# UC3844_-_SIN_TEST_GENERA_MODELO.net
KiCad netlist of a schematic drawn in Altium Designer
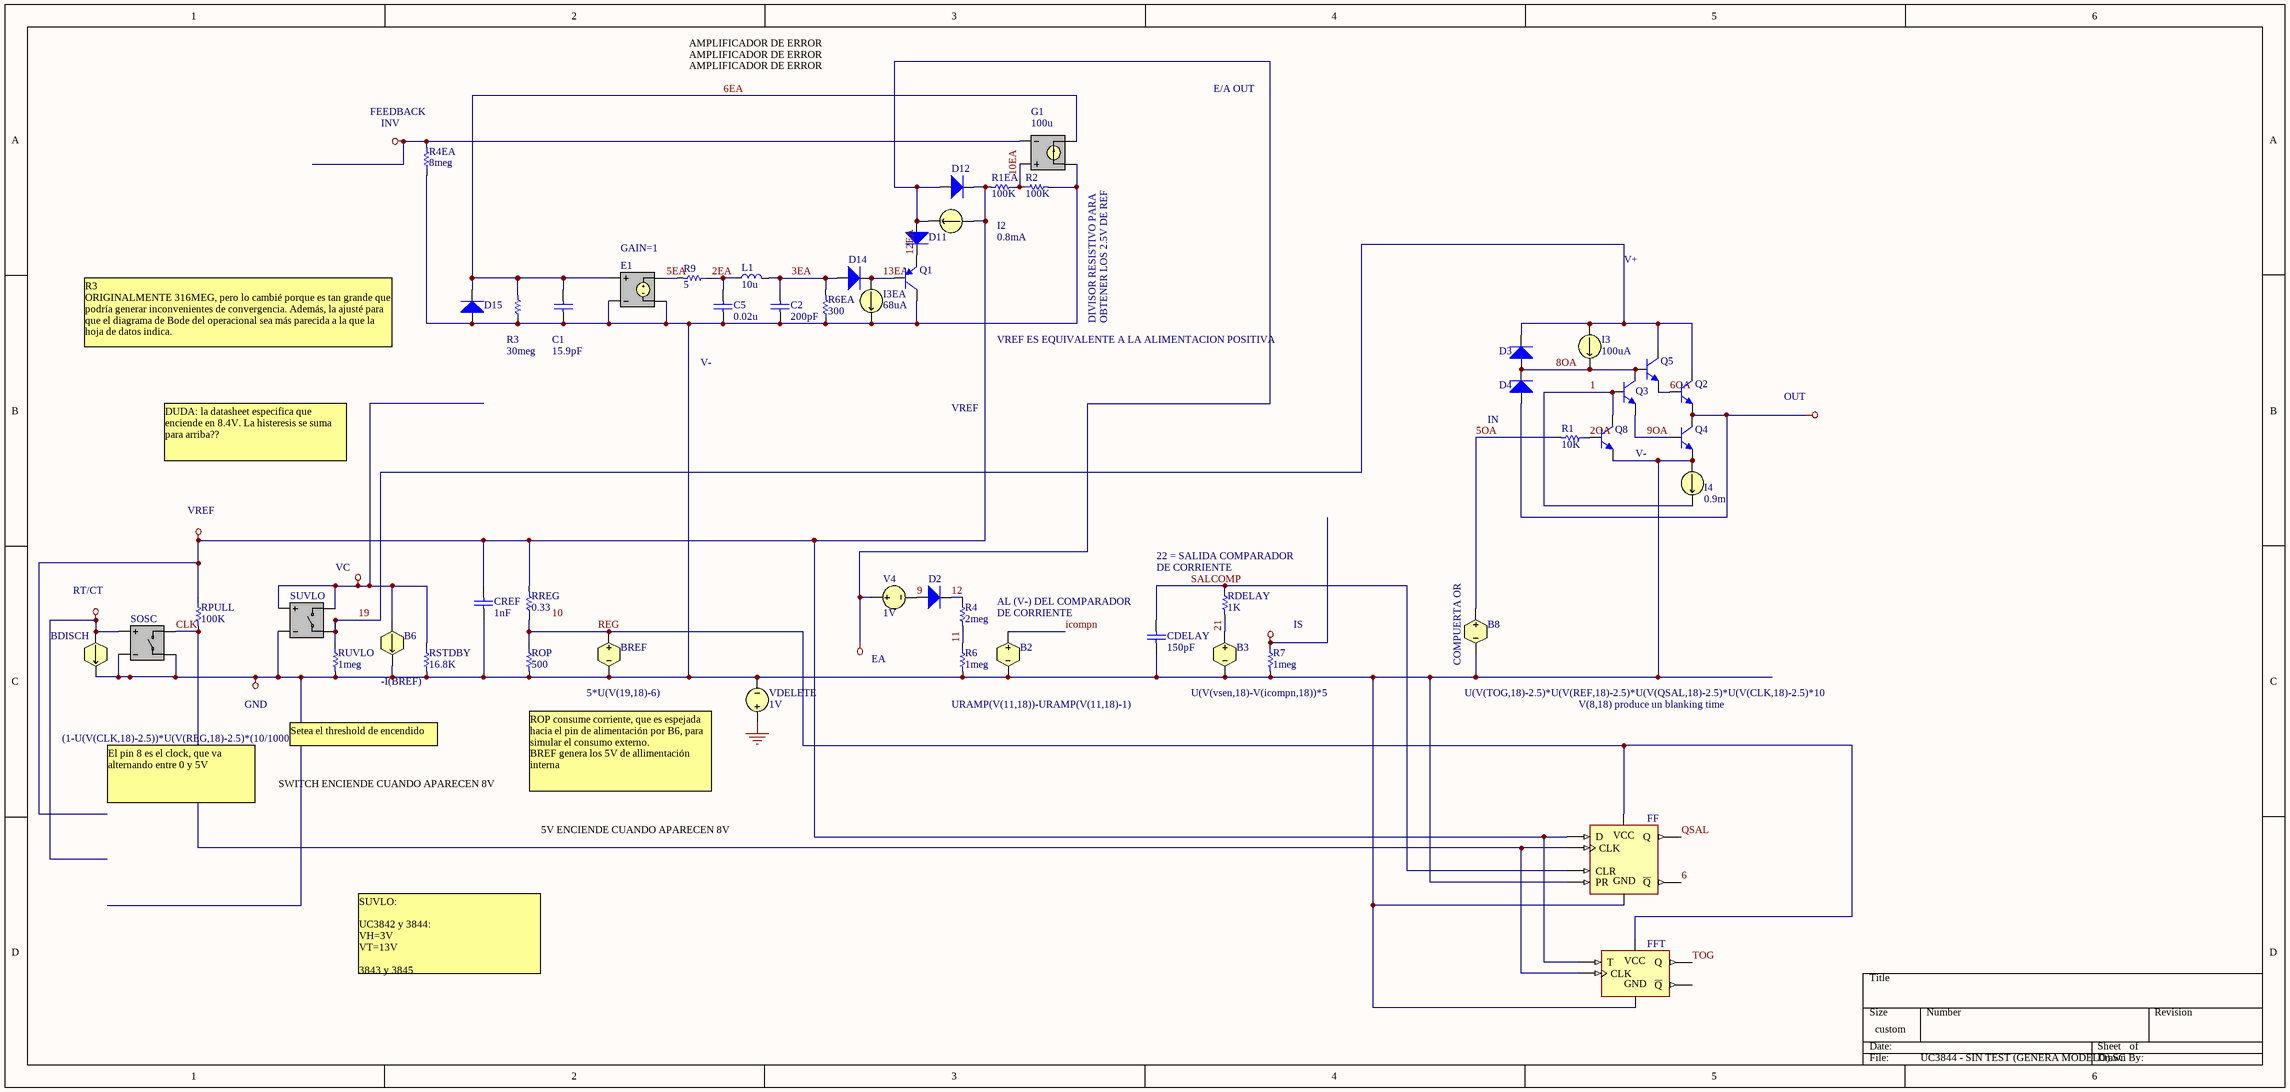
[diagram p0: UC3844 - SIN TEST (GENERA MODELO).SCHDOC]

(export (version "E")
  (design (tool "Eeschema 10.0.6"))
  (components
    (comp (ref "B2")
      (value "BVSRC")
      (description "Non-Linear Dependent Voltage Source")
      (fields
        (field (name "EQUATION") "URAMP(V(11,18))-URAMP(V(11,18)-1)")
        (field (name "PUBLISHER") "Altium Limited")
      )
      (libsource (lib "Simulation Sources") (part "BVSRC"))
    )
    (comp (ref "B3")
      (value "BVSRC")
      (description "Non-Linear Dependent Voltage Source")
      (fields
        (field (name "EQUATION") "U(V(vsen,18)-V(icompn,18))*5")
        (field (name "PUBLISHER") "Altium Limited")
      )
      (libsource (lib "Simulation Sources") (part "BVSRC"))
    )
    (comp (ref "B6")
      (value "BISRC")
      (description "Non-Linear Dependent Current Source")
      (fields (field (name "EQUATION") "-I(BREF)") (field (name "PUBLISHER") "Altium Limited"))
      (libsource (lib "Simulation Sources") (part "BISRC"))
    )
    (comp (ref "B8")
      (value "BVSRC")
      (description "Non-Linear Dependent Voltage Source")
      (fields
        (field (name "EQUATION") "U(V(TOG,18)-2.5)*U(V(REF,18)-2.5)*U(V(QSAL,18)-2.5)*U(V(CLK,18)-2.5)*10")
        (field (name "PUBLISHER") "Altium Limited")
      )
      (libsource (lib "Simulation Sources") (part "BVSRC"))
    )
    (comp (ref "BDISCH")
      (value "BISRC")
      (description "Non-Linear Dependent Current Source")
      (fields
        (field (name "EQUATION") "(1-U(V(CLK,18)-2.5))*U(V(REG,18)-2.5)*(10/1000)")
        (field (name "PUBLISHER") "Altium Limited")
      )
      (libsource (lib "Simulation Sources") (part "BISRC"))
    )
    (comp (ref "BREF")
      (value "BVSRC")
      (description "Non-Linear Dependent Voltage Source")
      (fields (field (name "EQUATION") "5*U(V(19,18)-6)") (field (name "PUBLISHER") "Altium Limited"))
      (libsource (lib "Simulation Sources") (part "BVSRC"))
    )
    (comp (ref "C1")
      (value "15.9pF")
      (footprint "0805")
      (description "Capacitor")
      (fields (field (name "VOLTAGE") "50V") (field (name "Comment") "Cap"))
      (libsource (lib "FEDE") (part "Cap"))
    )
    (comp (ref "C2")
      (value "200pF")
      (footprint "0805")
      (description "Capacitor")
      (fields (field (name "VOLTAGE") "50V") (field (name "Comment") "Cap"))
      (libsource (lib "FEDE") (part "Cap"))
    )
    (comp (ref "C5")
      (value "0.02u")
      (footprint "0805")
      (description "Capacitor")
      (fields (field (name "VOLTAGE") "50V") (field (name "Comment") "Cap"))
      (libsource (lib "FEDE") (part "Cap"))
    )
    (comp (ref "CDELAY")
      (value "150pF")
      (footprint "0805")
      (description "Capacitor")
      (fields (field (name "VOLTAGE") "50V") (field (name "Comment") "Cap"))
      (libsource (lib "FEDE") (part "Cap"))
    )
    (comp (ref "CREF")
      (value "1nF")
      (footprint "0805")
      (description "Capacitor")
      (fields (field (name "VOLTAGE") "50V") (field (name "Comment") "Cap"))
      (libsource (lib "FEDE") (part "Cap"))
    )
    (comp (ref "D2")
      (value "Diode")
      (footprint "diode400")
      (description "Diodo")
      (libsource (lib "FEDE") (part "Diode"))
    )
    (comp (ref "D3")
      (value "Diode")
      (footprint "diode400")
      (description "Diodo")
      (libsource (lib "FEDE") (part "Diode"))
    )
    (comp (ref "D4")
      (value "Diode")
      (footprint "diode400")
      (description "Diodo")
      (libsource (lib "FEDE") (part "Diode"))
    )
    (comp (ref "D11")
      (value "Diode")
      (footprint "diode400")
      (description "Diodo")
      (libsource (lib "FEDE") (part "Diode"))
    )
    (comp (ref "D12")
      (value "Diode")
      (footprint "diode400")
      (description "Diodo")
      (libsource (lib "FEDE") (part "Diode"))
    )
    (comp (ref "D14")
      (value "Diode")
      (footprint "diode400")
      (description "Diodo")
      (libsource (lib "FEDE") (part "Diode"))
    )
    (comp (ref "D15")
      (value "Diode")
      (footprint "diode400")
      (description "Diodo")
      (libsource (lib "FEDE") (part "Diode"))
    )
    (comp (ref "E1")
      (value "ESRC")
      (description "Voltage Controlled Voltage Source")
      (fields (field (name "PUBLISHER") "Altium Limited"))
      (libsource (lib "Simulation Sources") (part "ESRC"))
    )
    (comp (ref "FF")
      (value "FFSRV2")
      (description "D-Type Positive-Edge-Triggered Flip-Flop with Clear and Preset (simulación)")
      (libsource (lib "FEDE") (part "FFSRV2"))
    )
    (comp (ref "FFT")
      (value "FFT")
      (description "Positive-Edge-Triggered Flip-Flop T (simulación)")
      (libsource (lib "FEDE") (part "FFT"))
    )
    (comp (ref "G1")
      (value "GSRC")
      (description "Voltage Controlled Current Source")
      (fields (field (name "GAIN") "100u") (field (name "PUBLISHER") "Altium Limited"))
      (libsource (lib "Simulation Sources") (part "GSRC"))
    )
    (comp (ref "I2")
      (value "0.8mA")
      (description "Current Source")
      (fields (field (name "Comment") "ISRC") (field (name "PUBLISHER") "Altium Limited"))
      (libsource (lib "Simulation Sources") (part "ISRC"))
    )
    (comp (ref "I3")
      (value "100uA")
      (description "Current Source")
      (fields (field (name "Comment") "ISRC") (field (name "PUBLISHER") "Altium Limited"))
      (libsource (lib "Simulation Sources") (part "ISRC"))
    )
    (comp (ref "I3EA")
      (value "68uA")
      (description "Current Source")
      (fields (field (name "Comment") "ISRC") (field (name "PUBLISHER") "Altium Limited"))
      (libsource (lib "Simulation Sources") (part "ISRC"))
    )
    (comp (ref "I4")
      (value "0.9m")
      (description "Current Source")
      (fields (field (name "Comment") "ISRC") (field (name "PUBLISHER") "Altium Limited"))
      (libsource (lib "Simulation Sources") (part "ISRC"))
    )
    (comp (ref "L1")
      (value "10u")
      (footprint "TOROIDE TN14-9-5")
      (description "Inductor")
      (fields (field (name "Comment") "Inductor2"))
      (libsource (lib "FEDE") (part "Inductor2"))
    )
    (comp (ref "Q1")
      (value "PNP")
      (footprint "SOT23")
      (description "PNP Bipolar Transistor")
      (libsource (lib "FEDE") (part "PNP"))
    )
    (comp (ref "Q2")
      (value "NPN")
      (footprint "SOT23")
      (description "NPN Bipolar Transistor")
      (libsource (lib "FEDE") (part "NPN"))
    )
    (comp (ref "Q3")
      (value "NPN")
      (footprint "SOT23")
      (description "NPN Bipolar Transistor")
      (libsource (lib "FEDE") (part "NPN"))
    )
    (comp (ref "Q4")
      (value "NPN")
      (footprint "SOT23")
      (description "NPN Bipolar Transistor")
      (libsource (lib "FEDE") (part "NPN"))
    )
    (comp (ref "Q5")
      (value "NPN")
      (footprint "SOT23")
      (description "NPN Bipolar Transistor")
      (libsource (lib "FEDE") (part "NPN"))
    )
    (comp (ref "Q8")
      (value "NPN")
      (footprint "SOT23")
      (description "NPN Bipolar Transistor")
      (libsource (lib "FEDE") (part "NPN"))
    )
    (comp (ref "R1")
      (value "10K")
      (footprint "0805")
      (description "Resistor")
      (fields (field (name "POWER") "0.25W") (field (name "Comment") "Res"))
      (libsource (lib "FEDE") (part "Res"))
    )
    (comp (ref "R1EA")
      (value "100K")
      (footprint "0805")
      (description "Resistor")
      (fields (field (name "POWER") "0.25W") (field (name "Comment") "Res"))
      (libsource (lib "FEDE") (part "Res"))
    )
    (comp (ref "R2")
      (value "100K")
      (footprint "0805")
      (description "Resistor")
      (fields (field (name "POWER") "0.25W") (field (name "Comment") "Res"))
      (libsource (lib "FEDE") (part "Res"))
    )
    (comp (ref "R3")
      (value "30meg")
      (footprint "0805")
      (description "Resistor")
      (fields (field (name "POWER") "0.25W") (field (name "Comment") "Res"))
      (libsource (lib "FEDE") (part "Res"))
    )
    (comp (ref "R4")
      (value "2meg")
      (footprint "0805")
      (description "Resistor")
      (fields (field (name "POWER") "0.25W") (field (name "Comment") "Res"))
      (libsource (lib "FEDE") (part "Res"))
    )
    (comp (ref "R4EA")
      (value "8meg")
      (footprint "0805")
      (description "Resistor")
      (fields (field (name "POWER") "0.25W") (field (name "Comment") "Res"))
      (libsource (lib "FEDE") (part "Res"))
    )
    (comp (ref "R6")
      (value "1meg")
      (footprint "0805")
      (description "Resistor")
      (fields (field (name "POWER") "0.25W") (field (name "Comment") "Res"))
      (libsource (lib "FEDE") (part "Res"))
    )
    (comp (ref "R6EA")
      (value "300")
      (footprint "0805")
      (description "Resistor")
      (fields (field (name "POWER") "0.25W") (field (name "Comment") "Res"))
      (libsource (lib "FEDE") (part "Res"))
    )
    (comp (ref "R7")
      (value "1meg")
      (footprint "0805")
      (description "Resistor")
      (fields (field (name "POWER") "0.25W") (field (name "Comment") "Res"))
      (libsource (lib "FEDE") (part "Res"))
    )
    (comp (ref "R9")
      (value "5")
      (footprint "0805")
      (description "Resistor")
      (fields (field (name "POWER") "0.25W") (field (name "Comment") "Res"))
      (libsource (lib "FEDE") (part "Res"))
    )
    (comp (ref "RDELAY")
      (value "1K")
      (footprint "0805")
      (description "Resistor")
      (fields (field (name "POWER") "0.25W") (field (name "Comment") "Res"))
      (libsource (lib "FEDE") (part "Res"))
    )
    (comp (ref "ROP")
      (value "500")
      (footprint "0805")
      (description "Resistor")
      (fields (field (name "POWER") "0.25W") (field (name "Comment") "Res"))
      (libsource (lib "FEDE") (part "Res"))
    )
    (comp (ref "RPULL")
      (value "100K")
      (footprint "0805")
      (description "Resistor")
      (fields (field (name "POWER") "0.25W") (field (name "Comment") "Res"))
      (libsource (lib "FEDE") (part "Res"))
    )
    (comp (ref "RREG")
      (value "0.33")
      (footprint "0805")
      (description "Resistor")
      (fields (field (name "POWER") "0.25W") (field (name "Comment") "Res"))
      (libsource (lib "FEDE") (part "Res"))
    )
    (comp (ref "RSTDBY")
      (value "16.8K")
      (footprint "0805")
      (description "Resistor")
      (fields (field (name "POWER") "0.25W") (field (name "Comment") "Res"))
      (libsource (lib "FEDE") (part "Res"))
    )
    (comp (ref "RUVLO")
      (value "1meg")
      (footprint "0805")
      (description "Resistor")
      (fields (field (name "POWER") "0.25W") (field (name "Comment") "Res"))
      (libsource (lib "FEDE") (part "Res"))
    )
    (comp (ref "SOSC")
      (value "VSW")
      (description "Voltage Controlled Switch (simulación)")
      (libsource (lib "FEDE") (part "VSW"))
    )
    (comp (ref "SUVLO")
      (value "VSW")
      (description "Voltage Controlled Switch (simulación)")
      (libsource (lib "FEDE") (part "VSW"))
    )
    (comp (ref "V4")
      (value "1V")
      (description "Voltage Source")
      (fields (field (name "Comment") "VSRC") (field (name "PUBLISHER") "Altium Limited"))
      (libsource (lib "Simulation Sources") (part "VSRC"))
    )
    (comp (ref "VDELETE")
      (value "1V")
      (description "Voltage Source")
      (fields (field (name "Comment") "VSRC") (field (name "PUBLISHER") "Altium Limited"))
      (libsource (lib "Simulation Sources") (part "VSRC"))
    )
  )
  (nets
    (net (code "1") (name "/1") (class "Default")
      (node (ref "I4") (pin "2") (pinfunction "2_2") (pintype "passive"))
      (node (ref "Q3") (pin "2") (pinfunction "B_2") (pintype "passive"))
      (node (ref "Q8") (pin "1") (pinfunction "C_1") (pintype "passive"))
    )
    (net (code "2") (name "/2EA") (class "Default")
      (node (ref "C5") (pin "2") (pinfunction "2_2") (pintype "passive"))
      (node (ref "L1") (pin "1") (pinfunction "1_1") (pintype "passive"))
      (node (ref "R9") (pin "1") (pinfunction "1_1") (pintype "passive"))
    )
    (net (code "3") (name "/2OA") (class "Default")
      (node (ref "Q8") (pin "2") (pinfunction "B_2") (pintype "passive"))
      (node (ref "R1") (pin "1") (pinfunction "1_1") (pintype "passive"))
    )
    (net (code "4") (name "/3EA") (class "Default")
      (node (ref "C2") (pin "2") (pinfunction "2_2") (pintype "passive"))
      (node (ref "D14") (pin "1") (pinfunction "1_1") (pintype "passive"))
      (node (ref "L1") (pin "2") (pinfunction "2_2") (pintype "passive"))
      (node (ref "R6EA") (pin "2") (pinfunction "2_2") (pintype "passive"))
    )
    (net (code "5") (name "/5EA") (class "Default")
      (node (ref "E1") (pin "3") (pinfunction "N+_3") (pintype "passive"))
      (node (ref "R9") (pin "2") (pinfunction "2_2") (pintype "passive"))
    )
    (net (code "6") (name "/5OA") (class "Default")
      (node (ref "B8") (pin "1") (pinfunction "1_1") (pintype "passive"))
      (node (ref "R1") (pin "2") (pinfunction "2_2") (pintype "passive"))
    )
    (net (code "7") (name "/6") (class "Default")
      (node (ref "FF") (pin "6") (pinfunction "~{Q}_6") (pintype "output"))
    )
    (net (code "8") (name "/6EA") (class "Default")
      (node (ref "C1") (pin "2") (pinfunction "2_2") (pintype "passive"))
      (node (ref "D15") (pin "2") (pinfunction "2_2") (pintype "passive"))
      (node (ref "E1") (pin "1") (pinfunction "NC+_1") (pintype "passive"))
      (node (ref "G1") (pin "4") (pinfunction "N-_4") (pintype "passive"))
      (node (ref "R3") (pin "2") (pinfunction "2_2") (pintype "passive"))
    )
    (net (code "9") (name "/6OA") (class "Default")
      (node (ref "Q2") (pin "2") (pinfunction "B_2") (pintype "passive"))
      (node (ref "Q5") (pin "3") (pinfunction "E_3") (pintype "passive"))
    )
    (net (code "10") (name "/8OA") (class "Default")
      (node (ref "D3") (pin "1") (pinfunction "1_1") (pintype "passive"))
      (node (ref "D4") (pin "2") (pinfunction "2_2") (pintype "passive"))
      (node (ref "I3") (pin "2") (pinfunction "2_2") (pintype "passive"))
      (node (ref "Q3") (pin "1") (pinfunction "C_1") (pintype "passive"))
      (node (ref "Q5") (pin "2") (pinfunction "B_2") (pintype "passive"))
    )
    (net (code "11") (name "/9") (class "Default")
      (node (ref "D2") (pin "1") (pinfunction "1_1") (pintype "passive"))
      (node (ref "V4") (pin "2") (pinfunction "2_2") (pintype "passive"))
    )
    (net (code "12") (name "/9OA") (class "Default")
      (node (ref "Q3") (pin "3") (pinfunction "E_3") (pintype "passive"))
      (node (ref "Q4") (pin "2") (pinfunction "B_2") (pintype "passive"))
    )
    (net (code "14") (name "/10EA") (class "Default")
      (node (ref "G1") (pin "1") (pinfunction "NC+_1") (pintype "passive"))
      (node (ref "R1EA") (pin "1") (pinfunction "1_1") (pintype "passive"))
      (node (ref "R2") (pin "1") (pinfunction "1_1") (pintype "passive"))
    )
    (net (code "15") (name "/11") (class "Default")
      (node (ref "R4") (pin "2") (pinfunction "2_2") (pintype "passive"))
      (node (ref "R6") (pin "1") (pinfunction "1_1") (pintype "passive"))
    )
    (net (code "16") (name "/12") (class "Default")
      (node (ref "D2") (pin "2") (pinfunction "2_2") (pintype "passive"))
      (node (ref "R4") (pin "1") (pinfunction "1_1") (pintype "passive"))
    )
    (net (code "17") (name "/12EA") (class "Default")
      (node (ref "D11") (pin "2") (pinfunction "2_2") (pintype "passive"))
      (node (ref "Q1") (pin "3") (pinfunction "E_3") (pintype "passive"))
    )
    (net (code "18") (name "/13EA") (class "Default")
      (node (ref "D14") (pin "2") (pinfunction "2_2") (pintype "passive"))
      (node (ref "I3EA") (pin "1") (pinfunction "1_1") (pintype "passive"))
      (node (ref "Q1") (pin "2") (pinfunction "B_2") (pintype "passive"))
    )
    (net (code "19") (name "/19") (class "Default")
      (node (ref "D3") (pin "2") (pinfunction "2_2") (pintype "passive"))
      (node (ref "I3") (pin "1") (pinfunction "1_1") (pintype "passive"))
      (node (ref "Q2") (pin "1") (pinfunction "C_1") (pintype "passive"))
      (node (ref "Q5") (pin "1") (pinfunction "C_1") (pintype "passive"))
      (node (ref "RUVLO") (pin "1") (pinfunction "1_1") (pintype "passive"))
      (node (ref "SUVLO") (pin "4") (pinfunction "N2-_4") (pintype "passive"))
    )
    (net (code "20") (name "/21") (class "Default")
      (node (ref "B3") (pin "1") (pinfunction "1_1") (pintype "passive"))
      (node (ref "RDELAY") (pin "2") (pinfunction "2_2") (pintype "passive"))
    )
    (net (code "21") (name "/CLK") (class "Default")
      (node (ref "FF") (pin "3") (pinfunction "CLK_3") (pintype "input"))
      (node (ref "FFT") (pin "2") (pinfunction "CLK_2") (pintype "input"))
      (node (ref "RPULL") (pin "2") (pinfunction "2_2") (pintype "passive"))
      (node (ref "SOSC") (pin "3") (pinfunction "N2+_3") (pintype "passive"))
    )
    (net (code "22") (name "/QSAL") (class "Default")
      (node (ref "FF") (pin "5") (pinfunction "Q_5") (pintype "output"))
    )
    (net (code "23") (name "/REG") (class "Default")
      (node (ref "BREF") (pin "1") (pinfunction "1_1") (pintype "passive"))
      (node (ref "FF") (pin "14") (pinfunction "VCC_14") (pintype "power_in"))
      (node (ref "FFT") (pin "5") (pinfunction "VCC_5") (pintype "power_in"))
      (node (ref "ROP") (pin "1") (pinfunction "1_1") (pintype "passive"))
      (node (ref "RREG") (pin "1") (pinfunction "1_1") (pintype "passive"))
    )
    (net (code "24") (name "/SALCOMP") (class "Default")
      (node (ref "CDELAY") (pin "2") (pinfunction "2_2") (pintype "passive"))
      (node (ref "FF") (pin "1") (pinfunction "CLR_1") (pintype "input"))
      (node (ref "RDELAY") (pin "1") (pinfunction "1_1") (pintype "passive"))
    )
    (net (code "25") (name "/TOG") (class "Default")
      (node (ref "FFT") (pin "3") (pinfunction "Q_3") (pintype "output"))
    )
    (net (code "26") (name "/icompn") (class "Default")
      (node (ref "B2") (pin "1") (pinfunction "1_1") (pintype "passive"))
    )
    (net (code "27") (name "18") (class "Default")
      (node (ref "B2") (pin "2") (pinfunction "2_2") (pintype "passive"))
      (node (ref "B3") (pin "2") (pinfunction "2_2") (pintype "passive"))
      (node (ref "B6") (pin "2") (pinfunction "2_2") (pintype "passive"))
      (node (ref "B8") (pin "2") (pinfunction "2_2") (pintype "passive"))
      (node (ref "BDISCH") (pin "2") (pinfunction "2_2") (pintype "passive"))
      (node (ref "BREF") (pin "2") (pinfunction "2_2") (pintype "passive"))
      (node (ref "C1") (pin "1") (pinfunction "1_1") (pintype "passive"))
      (node (ref "C2") (pin "1") (pinfunction "1_1") (pintype "passive"))
      (node (ref "C5") (pin "1") (pinfunction "1_1") (pintype "passive"))
      (node (ref "CDELAY") (pin "1") (pinfunction "1_1") (pintype "passive"))
      (node (ref "CREF") (pin "1") (pinfunction "1_1") (pintype "passive"))
      (node (ref "D15") (pin "1") (pinfunction "1_1") (pintype "passive"))
      (node (ref "E1") (pin "2") (pinfunction "NC-_2") (pintype "passive"))
      (node (ref "E1") (pin "4") (pinfunction "N-_4") (pintype "passive"))
      (node (ref "FF") (pin "4") (pinfunction "PR_4") (pintype "input"))
      (node (ref "FF") (pin "7") (pinfunction "GND_7") (pintype "power_in"))
      (node (ref "FFT") (pin "6") (pinfunction "GND_6") (pintype "power_in"))
      (node (ref "G1") (pin "3") (pinfunction "N+_3") (pintype "passive"))
      (node (ref "I3EA") (pin "2") (pinfunction "2_2") (pintype "passive"))
      (node (ref "I4") (pin "1") (pinfunction "1_1") (pintype "passive"))
      (node (ref "Q1") (pin "1") (pinfunction "C_1") (pintype "passive"))
      (node (ref "Q4") (pin "3") (pinfunction "E_3") (pintype "passive"))
      (node (ref "Q8") (pin "3") (pinfunction "E_3") (pintype "passive"))
      (node (ref "R2") (pin "2") (pinfunction "2_2") (pintype "passive"))
      (node (ref "R3") (pin "1") (pinfunction "1_1") (pintype "passive"))
      (node (ref "R4EA") (pin "1") (pinfunction "1_1") (pintype "passive"))
      (node (ref "R6") (pin "2") (pinfunction "2_2") (pintype "passive"))
      (node (ref "R6EA") (pin "1") (pinfunction "1_1") (pintype "passive"))
      (node (ref "R7") (pin "2") (pinfunction "2_2") (pintype "passive"))
      (node (ref "ROP") (pin "2") (pinfunction "2_2") (pintype "passive"))
      (node (ref "RSTDBY") (pin "2") (pinfunction "2_2") (pintype "passive"))
      (node (ref "RUVLO") (pin "2") (pinfunction "2_2") (pintype "passive"))
      (node (ref "SOSC") (pin "2") (pinfunction "N1-_2") (pintype "passive"))
      (node (ref "SOSC") (pin "4") (pinfunction "N2-_4") (pintype "passive"))
      (node (ref "SUVLO") (pin "2") (pinfunction "N1-_2") (pintype "passive"))
      (node (ref "VDELETE") (pin "2") (pinfunction "2_2") (pintype "passive"))
    )
    (net (code "28") (name "ALIM") (class "Default")
      (node (ref "B6") (pin "1") (pinfunction "1_1") (pintype "passive"))
      (node (ref "RSTDBY") (pin "1") (pinfunction "1_1") (pintype "passive"))
      (node (ref "SUVLO") (pin "1") (pinfunction "N1+_1") (pintype "passive"))
      (node (ref "SUVLO") (pin "3") (pinfunction "N2+_3") (pintype "passive"))
    )
    (net (code "29") (name "EAOUTP") (class "Default")
      (node (ref "D11") (pin "1") (pinfunction "1_1") (pintype "passive"))
      (node (ref "D12") (pin "1") (pinfunction "1_1") (pintype "passive"))
      (node (ref "I2") (pin "2") (pinfunction "2_2") (pintype "passive"))
      (node (ref "V4") (pin "1") (pinfunction "1_1") (pintype "passive"))
    )
    (net (code "30") (name "FEED") (class "Default")
      (node (ref "G1") (pin "2") (pinfunction "NC-_2") (pintype "passive"))
      (node (ref "R4EA") (pin "2") (pinfunction "2_2") (pintype "passive"))
    )
    (net (code "31") (name "GND") (class "Default")
      (node (ref "VDELETE") (pin "1") (pinfunction "1_1") (pintype "passive"))
    )
    (net (code "32") (name "OUTP") (class "Default")
      (node (ref "D4") (pin "1") (pinfunction "1_1") (pintype "passive"))
      (node (ref "Q2") (pin "3") (pinfunction "E_3") (pintype "passive"))
      (node (ref "Q4") (pin "1") (pinfunction "C_1") (pintype "passive"))
    )
    (net (code "33") (name "REF") (class "Default")
      (node (ref "CREF") (pin "2") (pinfunction "2_2") (pintype "passive"))
      (node (ref "D12") (pin "2") (pinfunction "2_2") (pintype "passive"))
      (node (ref "FF") (pin "2") (pinfunction "D_2") (pintype "input"))
      (node (ref "FFT") (pin "1") (pinfunction "T_1") (pintype "input"))
      (node (ref "I2") (pin "1") (pinfunction "1_1") (pintype "passive"))
      (node (ref "R1EA") (pin "2") (pinfunction "2_2") (pintype "passive"))
      (node (ref "RPULL") (pin "1") (pinfunction "1_1") (pintype "passive"))
      (node (ref "RREG") (pin "2") (pinfunction "2_2") (pintype "passive"))
    )
    (net (code "34") (name "RTCT") (class "Default")
      (node (ref "BDISCH") (pin "1") (pinfunction "1_1") (pintype "passive"))
      (node (ref "SOSC") (pin "1") (pinfunction "N1+_1") (pintype "passive"))
    )
    (net (code "35") (name "VSEN") (class "Default")
      (node (ref "R7") (pin "1") (pinfunction "1_1") (pintype "passive"))
    )
    (net (code "36") (name "unconnected-(FFT-~{Q}-Pad4)") (class "Default")
      (node (ref "FFT") (pin "4") (pinfunction "~{Q}_4") (pintype "output"))
    )
  )
)
